# MAX9924_A2_MODE_schematic.net
KiCad netlist of a schematic drawn in EAGLE
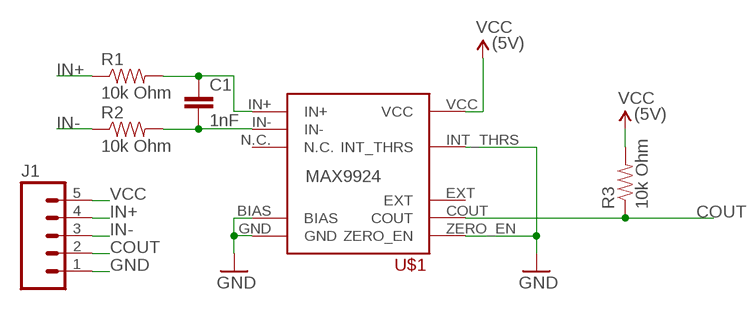
[diagram p0: schematic, sheet 1]

(export (version "E")
  (design (tool "Eeschema 10.0.6"))
  (components
    (comp (ref "C1")
      (value "1nF")
      (footprint "eagle-import:CAP-PTH-SMALL")
      (libsource (lib "eagle-import") (part "CAPPTH"))
    )
    (comp (ref "J1")
      (value "M05PTH")
      (footprint "eagle-import:1X05")
      (libsource (lib "eagle-import") (part "M05PTH"))
    )
    (comp (ref "R1")
      (value "10k Ohm")
      (footprint "eagle-import:AXIAL-0.4")
      (libsource (lib "eagle-import") (part "RESISTORPTH-1/4W"))
    )
    (comp (ref "R2")
      (value "10k Ohm")
      (footprint "eagle-import:AXIAL-0.4")
      (libsource (lib "eagle-import") (part "RESISTORPTH-1/4W"))
    )
    (comp (ref "R3")
      (value "10k Ohm")
      (footprint "eagle-import:AXIAL-0.4")
      (libsource (lib "eagle-import") (part "RESISTORPTH-1/4W"))
    )
    (comp (ref "U$1")
      (value "MAX9924")
      (footprint "eagle-import:MAX9924")
      (libsource (lib "eagle-import") (part "MAX9924"))
    )
  )
  (nets
    (net (code "1") (name "/COUT") (class "Default")
      (node (ref "J1") (pin "2") (pinfunction "2_2") (pintype "passive"))
      (node (ref "R3") (pin "P$1") (pinfunction "1_P$1") (pintype "passive"))
      (node (ref "U$1") (pin "COUT") (pinfunction "COUT_COUT") (pintype "output"))
    )
    (net (code "2") (name "/IN+") (class "Default")
      (node (ref "J1") (pin "4") (pinfunction "4_4") (pintype "passive"))
      (node (ref "R1") (pin "P$1") (pinfunction "1_P$1") (pintype "passive"))
    )
    (net (code "3") (name "/IN-") (class "Default")
      (node (ref "J1") (pin "3") (pinfunction "3_3") (pintype "passive"))
      (node (ref "R2") (pin "P$1") (pinfunction "1_P$1") (pintype "passive"))
    )
    (net (code "4") (name "GND") (class "Default")
      (node (ref "J1") (pin "1") (pinfunction "1_1") (pintype "passive"))
      (node (ref "U$1") (pin "BIAS") (pinfunction "BIAS_BIAS") (pintype "input"))
      (node (ref "U$1") (pin "GND") (pinfunction "GND_GND") (pintype "power_in"))
      (node (ref "U$1") (pin "INT_THRS") (pinfunction "INT_THRS_INT_THRS") (pintype "input"))
      (node (ref "U$1") (pin "ZERO_EN") (pinfunction "ZERO_EN_ZERO_EN") (pintype "input"))
    )
    (net (code "5") (name "Net-(R1-2)") (class "Default")
      (node (ref "C1") (pin "1") (pinfunction "1_1") (pintype "passive"))
      (node (ref "R1") (pin "P$2") (pinfunction "2_P$2") (pintype "passive"))
      (node (ref "U$1") (pin "IN+") (pinfunction "IN+_IN+") (pintype "input"))
    )
    (net (code "6") (name "Net-(R2-2)") (class "Default")
      (node (ref "C1") (pin "2") (pinfunction "2_2") (pintype "passive"))
      (node (ref "R2") (pin "P$2") (pinfunction "2_P$2") (pintype "passive"))
      (node (ref "U$1") (pin "IN-") (pinfunction "IN-_IN-") (pintype "input"))
    )
    (net (code "7") (name "VCC") (class "Default")
      (node (ref "J1") (pin "5") (pinfunction "5_5") (pintype "passive"))
      (node (ref "R3") (pin "P$2") (pinfunction "2_P$2") (pintype "passive"))
      (node (ref "U$1") (pin "VCC") (pinfunction "VCC_VCC") (pintype "power_in"))
    )
    (net (code "8") (name "unconnected-(U$1-PadEXT)") (class "Default")
      (node (ref "U$1") (pin "EXT") (pinfunction "EXT_EXT") (pintype "input"))
    )
    (net (code "9") (name "unconnected-(U$1-PadN.C.)") (class "Default")
      (node (ref "U$1") (pin "N.C.") (pinfunction "N.C._N.C.") (pintype "input"))
    )
  )
)
